# mk3-schield-samtec-vias.net
KiCad netlist of a schematic drawn in EAGLE
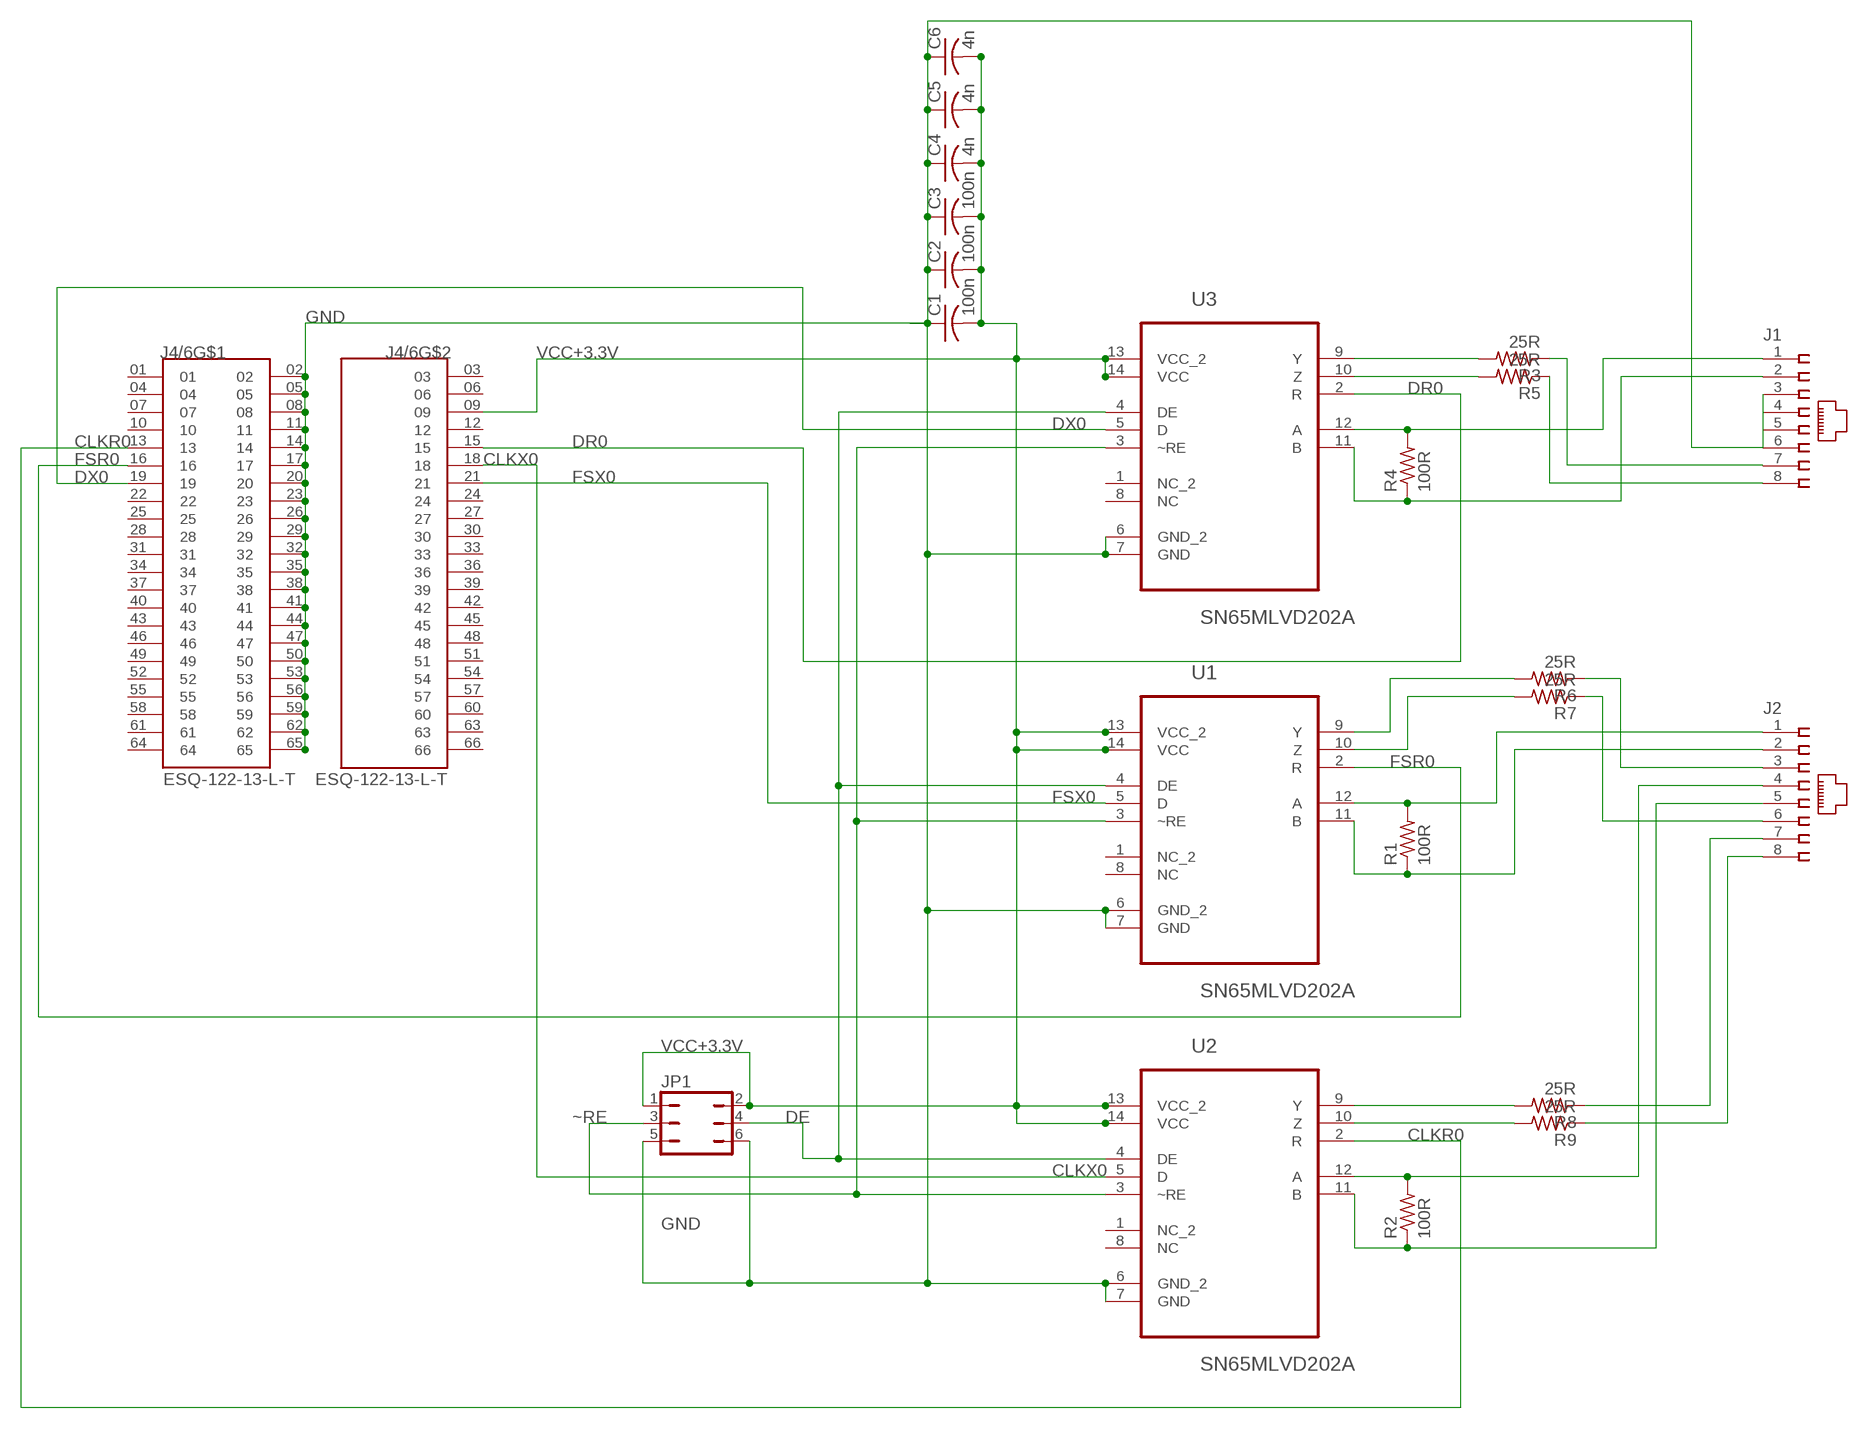
[diagram p0: schematic, sheet 1]

(export (version "E")
  (design (tool "Eeschema 10.0.6"))
  (components
    (comp (ref "C1")
      (value "100n")
      (footprint "eagle-import:C0805")
      (libsource (lib "eagle-import") (part "C-USC0805"))
    )
    (comp (ref "C2")
      (value "100n")
      (footprint "eagle-import:C0805")
      (libsource (lib "eagle-import") (part "C-USC0805"))
    )
    (comp (ref "C3")
      (value "100n")
      (footprint "eagle-import:C0805")
      (libsource (lib "eagle-import") (part "C-USC0805"))
    )
    (comp (ref "C4")
      (value "4n")
      (footprint "eagle-import:C0805")
      (libsource (lib "eagle-import") (part "C-USC0805"))
    )
    (comp (ref "C5")
      (value "4n")
      (footprint "eagle-import:C0805")
      (libsource (lib "eagle-import") (part "C-USC0805"))
    )
    (comp (ref "C6")
      (value "4n")
      (footprint "eagle-import:C0805")
      (libsource (lib "eagle-import") (part "C-USC0805"))
    )
    (comp (ref "J1")
      (value "557785-1-SHIELD")
      (footprint "eagle-import:557785-1")
      (libsource (lib "eagle-import") (part "557785-1-SHIELD"))
    )
    (comp (ref "J2")
      (value "557785-1-SHIELD")
      (footprint "eagle-import:557785-1")
      (libsource (lib "eagle-import") (part "557785-1-SHIELD"))
    )
    (comp (ref "J4/6")
      (value "ESQ-122-13-L-T")
      (footprint "eagle-import:SAMTEC_ESQ-122-13-L-T")
      (fields (field (name "MANUFACTURER") "Samtec"))
      (libsource (lib "eagle-import") (part "ESQ-122-13-L-T"))
    )
    (comp (ref "JP1")
      (value "JP3Q")
      (footprint "eagle-import:JP3Q")
      (libsource (lib "eagle-import") (part "JP3Q"))
    )
    (comp (ref "R1")
      (value "100R")
      (footprint "eagle-import:R0402")
      (libsource (lib "eagle-import") (part "R-US_R0402"))
    )
    (comp (ref "R2")
      (value "100R")
      (footprint "eagle-import:R0402")
      (libsource (lib "eagle-import") (part "R-US_R0402"))
    )
    (comp (ref "R3")
      (value "25R")
      (footprint "eagle-import:R0402")
      (libsource (lib "eagle-import") (part "R-US_R0402"))
    )
    (comp (ref "R4")
      (value "100R")
      (footprint "eagle-import:R0402")
      (libsource (lib "eagle-import") (part "R-US_R0402"))
    )
    (comp (ref "R5")
      (value "25R")
      (footprint "eagle-import:R0402")
      (libsource (lib "eagle-import") (part "R-US_R0402"))
    )
    (comp (ref "R6")
      (value "25R")
      (footprint "eagle-import:R0402")
      (libsource (lib "eagle-import") (part "R-US_R0402"))
    )
    (comp (ref "R7")
      (value "25R")
      (footprint "eagle-import:R0402")
      (libsource (lib "eagle-import") (part "R-US_R0402"))
    )
    (comp (ref "R8")
      (value "25R")
      (footprint "eagle-import:R0402")
      (libsource (lib "eagle-import") (part "R-US_R0402"))
    )
    (comp (ref "R9")
      (value "25R")
      (footprint "eagle-import:R0402")
      (libsource (lib "eagle-import") (part "R-US_R0402"))
    )
    (comp (ref "U1")
      (value "SN65MLVD202A")
      (footprint "eagle-import:SOIC127P600X175-14N")
      (fields (field (name "MPN") "SN65MLVD205AD"))
      (libsource (lib "eagle-import") (part "SN65MLVD205AD"))
    )
    (comp (ref "U2")
      (value "SN65MLVD202A")
      (footprint "eagle-import:SOIC127P600X175-14N")
      (fields (field (name "MPN") "SN65MLVD205AD"))
      (libsource (lib "eagle-import") (part "SN65MLVD205AD"))
    )
    (comp (ref "U3")
      (value "SN65MLVD202A")
      (footprint "eagle-import:SOIC127P600X175-14N")
      (fields (field (name "MPN") "SN65MLVD205AD"))
      (libsource (lib "eagle-import") (part "SN65MLVD205AD"))
    )
  )
  (nets
    (net (code "1") (name "/CLKR0") (class "Default")
      (node (ref "J4/6") (pin "13") (pinfunction "13_13") (pintype "passive"))
      (node (ref "U2") (pin "2") (pinfunction "R_2") (pintype "output"))
    )
    (net (code "2") (name "/CLKX0") (class "Default")
      (node (ref "J4/6") (pin "18") (pinfunction "18_18") (pintype "passive"))
      (node (ref "U2") (pin "5") (pinfunction "D_5") (pintype "input"))
    )
    (net (code "3") (name "/DE") (class "Default")
      (node (ref "JP1") (pin "4") (pinfunction "4_4") (pintype "passive"))
      (node (ref "U1") (pin "4") (pinfunction "DE_4") (pintype "input"))
      (node (ref "U2") (pin "4") (pinfunction "DE_4") (pintype "input"))
      (node (ref "U3") (pin "4") (pinfunction "DE_4") (pintype "input"))
    )
    (net (code "4") (name "/DR0") (class "Default")
      (node (ref "J4/6") (pin "15") (pinfunction "15_15") (pintype "passive"))
      (node (ref "U3") (pin "2") (pinfunction "R_2") (pintype "output"))
    )
    (net (code "5") (name "/DX0") (class "Default")
      (node (ref "J4/6") (pin "19") (pinfunction "19_19") (pintype "passive"))
      (node (ref "U3") (pin "5") (pinfunction "D_5") (pintype "input"))
    )
    (net (code "6") (name "/FSR0") (class "Default")
      (node (ref "J4/6") (pin "16") (pinfunction "16_16") (pintype "passive"))
      (node (ref "U1") (pin "2") (pinfunction "R_2") (pintype "output"))
    )
    (net (code "7") (name "/FSX0") (class "Default")
      (node (ref "J4/6") (pin "21") (pinfunction "21_21") (pintype "passive"))
      (node (ref "U1") (pin "5") (pinfunction "D_5") (pintype "input"))
    )
    (net (code "8") (name "/GND") (class "Default")
      (node (ref "C1") (pin "1") (pinfunction "1_1") (pintype "passive"))
      (node (ref "C2") (pin "1") (pinfunction "1_1") (pintype "passive"))
      (node (ref "C3") (pin "1") (pinfunction "1_1") (pintype "passive"))
      (node (ref "C4") (pin "1") (pinfunction "1_1") (pintype "passive"))
      (node (ref "C5") (pin "1") (pinfunction "1_1") (pintype "passive"))
      (node (ref "C6") (pin "1") (pinfunction "1_1") (pintype "passive"))
      (node (ref "J1") (pin "3") (pinfunction "3_3") (pintype "passive"))
      (node (ref "J1") (pin "4") (pinfunction "4_4") (pintype "passive"))
      (node (ref "J1") (pin "5") (pinfunction "5_5") (pintype "passive"))
      (node (ref "J1") (pin "6") (pinfunction "6_6") (pintype "passive"))
      (node (ref "J4/6") (pin "02") (pinfunction "02_02") (pintype "passive"))
      (node (ref "J4/6") (pin "05") (pinfunction "05_05") (pintype "passive"))
      (node (ref "J4/6") (pin "08") (pinfunction "08_08") (pintype "passive"))
      (node (ref "J4/6") (pin "11") (pinfunction "11_11") (pintype "passive"))
      (node (ref "J4/6") (pin "14") (pinfunction "14_14") (pintype "passive"))
      (node (ref "J4/6") (pin "17") (pinfunction "17_17") (pintype "passive"))
      (node (ref "J4/6") (pin "20") (pinfunction "20_20") (pintype "passive"))
      (node (ref "J4/6") (pin "23") (pinfunction "23_23") (pintype "passive"))
      (node (ref "J4/6") (pin "26") (pinfunction "26_26") (pintype "passive"))
      (node (ref "J4/6") (pin "29") (pinfunction "29_29") (pintype "passive"))
      (node (ref "J4/6") (pin "32") (pinfunction "32_32") (pintype "passive"))
      (node (ref "J4/6") (pin "35") (pinfunction "35_35") (pintype "passive"))
      (node (ref "J4/6") (pin "38") (pinfunction "38_38") (pintype "passive"))
      (node (ref "J4/6") (pin "41") (pinfunction "41_41") (pintype "passive"))
      (node (ref "J4/6") (pin "44") (pinfunction "44_44") (pintype "passive"))
      (node (ref "J4/6") (pin "47") (pinfunction "47_47") (pintype "passive"))
      (node (ref "J4/6") (pin "50") (pinfunction "50_50") (pintype "passive"))
      (node (ref "J4/6") (pin "53") (pinfunction "53_53") (pintype "passive"))
      (node (ref "J4/6") (pin "56") (pinfunction "56_56") (pintype "passive"))
      (node (ref "J4/6") (pin "59") (pinfunction "59_59") (pintype "passive"))
      (node (ref "J4/6") (pin "62") (pinfunction "62_62") (pintype "passive"))
      (node (ref "J4/6") (pin "65") (pinfunction "65_65") (pintype "passive"))
      (node (ref "JP1") (pin "5") (pinfunction "5_5") (pintype "passive"))
      (node (ref "JP1") (pin "6") (pinfunction "6_6") (pintype "passive"))
      (node (ref "U1") (pin "6") (pinfunction "GND_2_6") (pintype "passive"))
      (node (ref "U1") (pin "7") (pinfunction "GND_7") (pintype "passive"))
      (node (ref "U2") (pin "6") (pinfunction "GND_2_6") (pintype "passive"))
      (node (ref "U2") (pin "7") (pinfunction "GND_7") (pintype "passive"))
      (node (ref "U3") (pin "6") (pinfunction "GND_2_6") (pintype "passive"))
      (node (ref "U3") (pin "7") (pinfunction "GND_7") (pintype "passive"))
    )
    (net (code "9") (name "/VCC+3.3V") (class "Default")
      (node (ref "C1") (pin "2") (pinfunction "2_2") (pintype "passive"))
      (node (ref "C2") (pin "2") (pinfunction "2_2") (pintype "passive"))
      (node (ref "C3") (pin "2") (pinfunction "2_2") (pintype "passive"))
      (node (ref "C4") (pin "2") (pinfunction "2_2") (pintype "passive"))
      (node (ref "C5") (pin "2") (pinfunction "2_2") (pintype "passive"))
      (node (ref "C6") (pin "2") (pinfunction "2_2") (pintype "passive"))
      (node (ref "J4/6") (pin "09") (pinfunction "09_09") (pintype "passive"))
      (node (ref "JP1") (pin "1") (pinfunction "1_1") (pintype "passive"))
      (node (ref "JP1") (pin "2") (pinfunction "2_2") (pintype "passive"))
      (node (ref "U1") (pin "13") (pinfunction "VCC_2_13") (pintype "power_in"))
      (node (ref "U1") (pin "14") (pinfunction "VCC_14") (pintype "power_in"))
      (node (ref "U2") (pin "13") (pinfunction "VCC_2_13") (pintype "power_in"))
      (node (ref "U2") (pin "14") (pinfunction "VCC_14") (pintype "power_in"))
      (node (ref "U3") (pin "13") (pinfunction "VCC_2_13") (pintype "power_in"))
      (node (ref "U3") (pin "14") (pinfunction "VCC_14") (pintype "power_in"))
    )
    (net (code "10") (name "/~{RE}") (class "Default")
      (node (ref "JP1") (pin "3") (pinfunction "3_3") (pintype "passive"))
      (node (ref "U1") (pin "3") (pinfunction "~{RE}_3") (pintype "input"))
      (node (ref "U2") (pin "3") (pinfunction "~{RE}_3") (pintype "input"))
      (node (ref "U3") (pin "3") (pinfunction "~{RE}_3") (pintype "input"))
    )
    (net (code "11") (name "Net-(J1-Pad7)") (class "Default")
      (node (ref "J1") (pin "7") (pinfunction "7_7") (pintype "passive"))
      (node (ref "R3") (pin "1") (pinfunction "1_1") (pintype "passive"))
    )
    (net (code "12") (name "Net-(J1-Pad8)") (class "Default")
      (node (ref "J1") (pin "8") (pinfunction "8_8") (pintype "passive"))
      (node (ref "R5") (pin "1") (pinfunction "1_1") (pintype "passive"))
    )
    (net (code "13") (name "Net-(J2-Pad3)") (class "Default")
      (node (ref "J2") (pin "3") (pinfunction "3_3") (pintype "passive"))
      (node (ref "R6") (pin "1") (pinfunction "1_1") (pintype "passive"))
    )
    (net (code "14") (name "Net-(J2-Pad6)") (class "Default")
      (node (ref "J2") (pin "6") (pinfunction "6_6") (pintype "passive"))
      (node (ref "R7") (pin "1") (pinfunction "1_1") (pintype "passive"))
    )
    (net (code "15") (name "Net-(J2-Pad7)") (class "Default")
      (node (ref "J2") (pin "7") (pinfunction "7_7") (pintype "passive"))
      (node (ref "R8") (pin "1") (pinfunction "1_1") (pintype "passive"))
    )
    (net (code "16") (name "Net-(J2-Pad8)") (class "Default")
      (node (ref "J2") (pin "8") (pinfunction "8_8") (pintype "passive"))
      (node (ref "R9") (pin "1") (pinfunction "1_1") (pintype "passive"))
    )
    (net (code "17") (name "Net-(U1-A)") (class "Default")
      (node (ref "J2") (pin "1") (pinfunction "1_1") (pintype "passive"))
      (node (ref "R1") (pin "2") (pinfunction "2_2") (pintype "passive"))
      (node (ref "U1") (pin "12") (pinfunction "A_12") (pintype "output"))
    )
    (net (code "18") (name "Net-(U1-B)") (class "Default")
      (node (ref "J2") (pin "2") (pinfunction "2_2") (pintype "passive"))
      (node (ref "R1") (pin "1") (pinfunction "1_1") (pintype "passive"))
      (node (ref "U1") (pin "11") (pinfunction "B_11") (pintype "output"))
    )
    (net (code "19") (name "Net-(U1-Y)") (class "Default")
      (node (ref "R6") (pin "2") (pinfunction "2_2") (pintype "passive"))
      (node (ref "U1") (pin "9") (pinfunction "Y_9") (pintype "output"))
    )
    (net (code "20") (name "Net-(U1-Z)") (class "Default")
      (node (ref "R7") (pin "2") (pinfunction "2_2") (pintype "passive"))
      (node (ref "U1") (pin "10") (pinfunction "Z_10") (pintype "output"))
    )
    (net (code "21") (name "Net-(U2-A)") (class "Default")
      (node (ref "J2") (pin "4") (pinfunction "4_4") (pintype "passive"))
      (node (ref "R2") (pin "2") (pinfunction "2_2") (pintype "passive"))
      (node (ref "U2") (pin "12") (pinfunction "A_12") (pintype "output"))
    )
    (net (code "22") (name "Net-(U2-B)") (class "Default")
      (node (ref "J2") (pin "5") (pinfunction "5_5") (pintype "passive"))
      (node (ref "R2") (pin "1") (pinfunction "1_1") (pintype "passive"))
      (node (ref "U2") (pin "11") (pinfunction "B_11") (pintype "output"))
    )
    (net (code "23") (name "Net-(U2-Y)") (class "Default")
      (node (ref "R8") (pin "2") (pinfunction "2_2") (pintype "passive"))
      (node (ref "U2") (pin "9") (pinfunction "Y_9") (pintype "output"))
    )
    (net (code "24") (name "Net-(U2-Z)") (class "Default")
      (node (ref "R9") (pin "2") (pinfunction "2_2") (pintype "passive"))
      (node (ref "U2") (pin "10") (pinfunction "Z_10") (pintype "output"))
    )
    (net (code "25") (name "Net-(U3-A)") (class "Default")
      (node (ref "J1") (pin "1") (pinfunction "1_1") (pintype "passive"))
      (node (ref "R4") (pin "2") (pinfunction "2_2") (pintype "passive"))
      (node (ref "U3") (pin "12") (pinfunction "A_12") (pintype "output"))
    )
    (net (code "26") (name "Net-(U3-B)") (class "Default")
      (node (ref "J1") (pin "2") (pinfunction "2_2") (pintype "passive"))
      (node (ref "R4") (pin "1") (pinfunction "1_1") (pintype "passive"))
      (node (ref "U3") (pin "11") (pinfunction "B_11") (pintype "output"))
    )
    (net (code "27") (name "Net-(U3-Y)") (class "Default")
      (node (ref "R3") (pin "2") (pinfunction "2_2") (pintype "passive"))
      (node (ref "U3") (pin "9") (pinfunction "Y_9") (pintype "output"))
    )
    (net (code "28") (name "Net-(U3-Z)") (class "Default")
      (node (ref "R5") (pin "2") (pinfunction "2_2") (pintype "passive"))
      (node (ref "U3") (pin "10") (pinfunction "Z_10") (pintype "output"))
    )
    (net (code "29") (name "unconnected-(J4/6-Pad01)") (class "Default")
      (node (ref "J4/6") (pin "01") (pinfunction "01_01") (pintype "passive"))
    )
    (net (code "30") (name "unconnected-(J4/6-Pad03)") (class "Default")
      (node (ref "J4/6") (pin "03") (pinfunction "03_03") (pintype "passive"))
    )
    (net (code "31") (name "unconnected-(J4/6-Pad04)") (class "Default")
      (node (ref "J4/6") (pin "04") (pinfunction "04_04") (pintype "passive"))
    )
    (net (code "32") (name "unconnected-(J4/6-Pad06)") (class "Default")
      (node (ref "J4/6") (pin "06") (pinfunction "06_06") (pintype "passive"))
    )
    (net (code "33") (name "unconnected-(J4/6-Pad07)") (class "Default")
      (node (ref "J4/6") (pin "07") (pinfunction "07_07") (pintype "passive"))
    )
    (net (code "34") (name "unconnected-(J4/6-Pad10)") (class "Default")
      (node (ref "J4/6") (pin "10") (pinfunction "10_10") (pintype "passive"))
    )
    (net (code "35") (name "unconnected-(J4/6-Pad12)") (class "Default")
      (node (ref "J4/6") (pin "12") (pinfunction "12_12") (pintype "passive"))
    )
    (net (code "36") (name "unconnected-(J4/6-Pad22)") (class "Default")
      (node (ref "J4/6") (pin "22") (pinfunction "22_22") (pintype "passive"))
    )
    (net (code "37") (name "unconnected-(J4/6-Pad24)") (class "Default")
      (node (ref "J4/6") (pin "24") (pinfunction "24_24") (pintype "passive"))
    )
    (net (code "38") (name "unconnected-(J4/6-Pad25)") (class "Default")
      (node (ref "J4/6") (pin "25") (pinfunction "25_25") (pintype "passive"))
    )
    (net (code "39") (name "unconnected-(J4/6-Pad27)") (class "Default")
      (node (ref "J4/6") (pin "27") (pinfunction "27_27") (pintype "passive"))
    )
    (net (code "40") (name "unconnected-(J4/6-Pad28)") (class "Default")
      (node (ref "J4/6") (pin "28") (pinfunction "28_28") (pintype "passive"))
    )
    (net (code "41") (name "unconnected-(J4/6-Pad30)") (class "Default")
      (node (ref "J4/6") (pin "30") (pinfunction "30_30") (pintype "passive"))
    )
    (net (code "42") (name "unconnected-(J4/6-Pad31)") (class "Default")
      (node (ref "J4/6") (pin "31") (pinfunction "31_31") (pintype "passive"))
    )
    (net (code "43") (name "unconnected-(J4/6-Pad33)") (class "Default")
      (node (ref "J4/6") (pin "33") (pinfunction "33_33") (pintype "passive"))
    )
    (net (code "44") (name "unconnected-(J4/6-Pad34)") (class "Default")
      (node (ref "J4/6") (pin "34") (pinfunction "34_34") (pintype "passive"))
    )
    (net (code "45") (name "unconnected-(J4/6-Pad36)") (class "Default")
      (node (ref "J4/6") (pin "36") (pinfunction "36_36") (pintype "passive"))
    )
    (net (code "46") (name "unconnected-(J4/6-Pad37)") (class "Default")
      (node (ref "J4/6") (pin "37") (pinfunction "37_37") (pintype "passive"))
    )
    (net (code "47") (name "unconnected-(J4/6-Pad39)") (class "Default")
      (node (ref "J4/6") (pin "39") (pinfunction "39_39") (pintype "passive"))
    )
    (net (code "48") (name "unconnected-(J4/6-Pad40)") (class "Default")
      (node (ref "J4/6") (pin "40") (pinfunction "40_40") (pintype "passive"))
    )
    (net (code "49") (name "unconnected-(J4/6-Pad42)") (class "Default")
      (node (ref "J4/6") (pin "42") (pinfunction "42_42") (pintype "passive"))
    )
    (net (code "50") (name "unconnected-(J4/6-Pad43)") (class "Default")
      (node (ref "J4/6") (pin "43") (pinfunction "43_43") (pintype "passive"))
    )
    (net (code "51") (name "unconnected-(J4/6-Pad45)") (class "Default")
      (node (ref "J4/6") (pin "45") (pinfunction "45_45") (pintype "passive"))
    )
    (net (code "52") (name "unconnected-(J4/6-Pad46)") (class "Default")
      (node (ref "J4/6") (pin "46") (pinfunction "46_46") (pintype "passive"))
    )
    (net (code "53") (name "unconnected-(J4/6-Pad48)") (class "Default")
      (node (ref "J4/6") (pin "48") (pinfunction "48_48") (pintype "passive"))
    )
    (net (code "54") (name "unconnected-(J4/6-Pad49)") (class "Default")
      (node (ref "J4/6") (pin "49") (pinfunction "49_49") (pintype "passive"))
    )
    (net (code "55") (name "unconnected-(J4/6-Pad51)") (class "Default")
      (node (ref "J4/6") (pin "51") (pinfunction "51_51") (pintype "passive"))
    )
    (net (code "56") (name "unconnected-(J4/6-Pad52)") (class "Default")
      (node (ref "J4/6") (pin "52") (pinfunction "52_52") (pintype "passive"))
    )
    (net (code "57") (name "unconnected-(J4/6-Pad54)") (class "Default")
      (node (ref "J4/6") (pin "54") (pinfunction "54_54") (pintype "passive"))
    )
    (net (code "58") (name "unconnected-(J4/6-Pad55)") (class "Default")
      (node (ref "J4/6") (pin "55") (pinfunction "55_55") (pintype "passive"))
    )
    (net (code "59") (name "unconnected-(J4/6-Pad57)") (class "Default")
      (node (ref "J4/6") (pin "57") (pinfunction "57_57") (pintype "passive"))
    )
    (net (code "60") (name "unconnected-(J4/6-Pad58)") (class "Default")
      (node (ref "J4/6") (pin "58") (pinfunction "58_58") (pintype "passive"))
    )
    (net (code "61") (name "unconnected-(J4/6-Pad60)") (class "Default")
      (node (ref "J4/6") (pin "60") (pinfunction "60_60") (pintype "passive"))
    )
    (net (code "62") (name "unconnected-(J4/6-Pad61)") (class "Default")
      (node (ref "J4/6") (pin "61") (pinfunction "61_61") (pintype "passive"))
    )
    (net (code "63") (name "unconnected-(J4/6-Pad63)") (class "Default")
      (node (ref "J4/6") (pin "63") (pinfunction "63_63") (pintype "passive"))
    )
    (net (code "64") (name "unconnected-(J4/6-Pad64)") (class "Default")
      (node (ref "J4/6") (pin "64") (pinfunction "64_64") (pintype "passive"))
    )
    (net (code "65") (name "unconnected-(J4/6-Pad66)") (class "Default")
      (node (ref "J4/6") (pin "66") (pinfunction "66_66") (pintype "passive"))
    )
    (net (code "66") (name "unconnected-(U1-NC-Pad8)") (class "Default")
      (node (ref "U1") (pin "8") (pinfunction "NC_8") (pintype "no_connect"))
    )
    (net (code "67") (name "unconnected-(U1-NC_2-Pad1)") (class "Default")
      (node (ref "U1") (pin "1") (pinfunction "NC_2_1") (pintype "no_connect"))
    )
    (net (code "68") (name "unconnected-(U2-NC-Pad8)") (class "Default")
      (node (ref "U2") (pin "8") (pinfunction "NC_8") (pintype "no_connect"))
    )
    (net (code "69") (name "unconnected-(U2-NC_2-Pad1)") (class "Default")
      (node (ref "U2") (pin "1") (pinfunction "NC_2_1") (pintype "no_connect"))
    )
    (net (code "70") (name "unconnected-(U3-NC-Pad8)") (class "Default")
      (node (ref "U3") (pin "8") (pinfunction "NC_8") (pintype "no_connect"))
    )
    (net (code "71") (name "unconnected-(U3-NC_2-Pad1)") (class "Default")
      (node (ref "U3") (pin "1") (pinfunction "NC_2_1") (pintype "no_connect"))
    )
  )
)
